# INA219-surrounding.net
KiCad netlist of a schematic drawn in Altium Designer
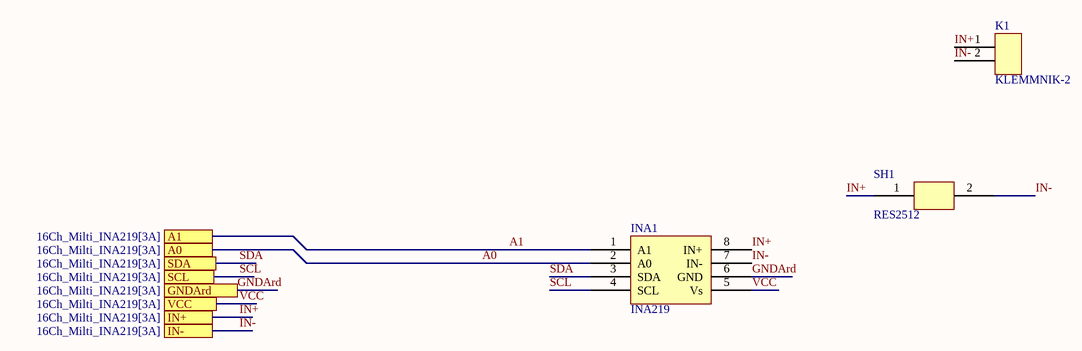
[diagram p0: INA219-surrounding.SchDoc]

(export (version "E")
  (design (tool "Eeschema 10.0.6"))
  (components
    (comp (ref "INA1") (value "INA219") (footprint "INA219") (libsource (lib "eic_lib") (part "INA219")))
    (comp (ref "K1")
      (value "KLEMMNIK-2")
      (footprint "KLEMMNIK-2")
      (libsource (lib "eic_lib") (part "KLEMMNIK-2"))
    )
    (comp (ref "SH1") (value "RES2512") (footprint "RES2512") (libsource (lib "eic_lib") (part "RES2512")))
  )
  (nets
    (net (code "1") (name "/A0") (class "Default")
      (node (ref "INA1") (pin "2") (pinfunction "A0_2") (pintype "passive"))
    )
    (net (code "2") (name "/A1") (class "Default")
      (node (ref "INA1") (pin "1") (pinfunction "A1_1") (pintype "passive"))
    )
    (net (code "3") (name "/GNDArd") (class "Default")
      (node (ref "INA1") (pin "6") (pinfunction "GND_6") (pintype "passive"))
    )
    (net (code "4") (name "/IN+") (class "Default")
      (node (ref "INA1") (pin "8") (pinfunction "IN+_8") (pintype "passive"))
      (node (ref "K1") (pin "1") (pintype "passive"))
      (node (ref "SH1") (pin "1") (pintype "passive"))
    )
    (net (code "5") (name "/IN-") (class "Default")
      (node (ref "INA1") (pin "7") (pinfunction "IN-_7") (pintype "passive"))
      (node (ref "K1") (pin "2") (pintype "passive"))
      (node (ref "SH1") (pin "2") (pintype "passive"))
    )
    (net (code "6") (name "/SCL") (class "Default")
      (node (ref "INA1") (pin "4") (pinfunction "SCL_4") (pintype "passive"))
    )
    (net (code "7") (name "/SDA") (class "Default")
      (node (ref "INA1") (pin "3") (pinfunction "SDA_3") (pintype "passive"))
    )
    (net (code "8") (name "/VCC") (class "Default")
      (node (ref "INA1") (pin "5") (pinfunction "Vs_5") (pintype "passive"))
    )
  )
)
